# 2_Thermal_stability.net
KiCad netlist of a schematic drawn in Altium Designer
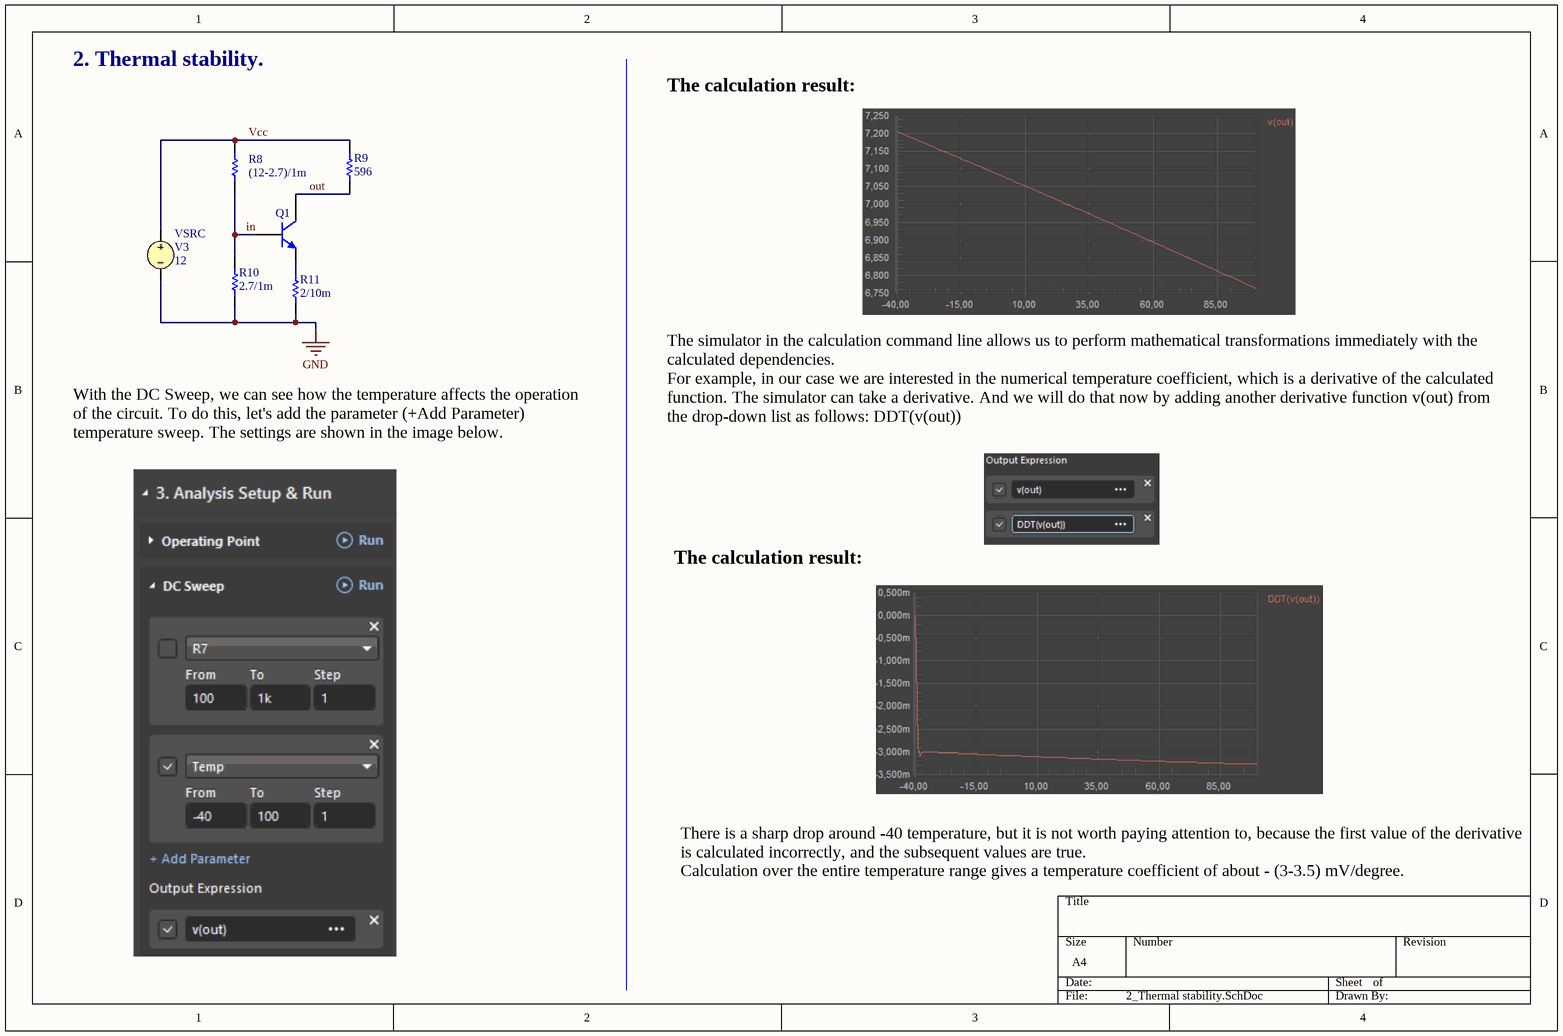
[diagram p0: 2_Thermal stability.SchDoc]

(export (version "E")
  (design (tool "Eeschema 10.0.6"))
  (components
    (comp (ref "Q1")
      (value "Bipolar  NPN 3 Pins  Transistor  Modified Version of the Gummel-Poon Model")
      (libsource (lib "Simulation Generic Components") (part "BJT NPN_MGP"))
    )
    (comp (ref "R8")
      (value "(12-2.7)/1m")
      (description "Resistor")
      (libsource (lib "Simulation Generic Components") (part "Resistor"))
    )
    (comp (ref "R9")
      (value "596")
      (description "Resistor")
      (libsource (lib "Simulation Generic Components") (part "Resistor"))
    )
    (comp (ref "R10")
      (value "2.7/1m")
      (description "Resistor")
      (libsource (lib "Simulation Generic Components") (part "Resistor"))
    )
    (comp (ref "R11")
      (value "2/10m")
      (description "Resistor")
      (libsource (lib "Simulation Generic Components") (part "Resistor"))
    )
    (comp (ref "V3")
      (value "VSRC")
      (description "Voltage Source")
      (fields (field (name "ALTIUM_VALUE") "12") (field (name "PUBLISHER") "Altium Limited"))
      (libsource (lib "Simulation Generic Components") (part "VSRC"))
    )
  )
  (nets
    (net (code "1") (name "/Vcc") (class "Default")
      (node (ref "R8") (pin "2") (pinfunction "2_2") (pintype "passive"))
      (node (ref "R9") (pin "2") (pinfunction "2_2") (pintype "passive"))
      (node (ref "V3") (pin "1") (pinfunction "1_1") (pintype "passive"))
    )
    (net (code "2") (name "/in") (class "Default")
      (node (ref "Q1") (pin "2") (pinfunction "B_2") (pintype "passive"))
      (node (ref "R10") (pin "1") (pinfunction "1_1") (pintype "passive"))
      (node (ref "R8") (pin "1") (pinfunction "1_1") (pintype "passive"))
    )
    (net (code "3") (name "/out") (class "Default")
      (node (ref "Q1") (pin "1") (pinfunction "C_1") (pintype "passive"))
      (node (ref "R9") (pin "1") (pinfunction "1_1") (pintype "passive"))
    )
    (net (code "4") (name "GND") (class "Default")
      (node (ref "R10") (pin "2") (pinfunction "2_2") (pintype "passive"))
      (node (ref "R11") (pin "1") (pinfunction "1_1") (pintype "passive"))
      (node (ref "V3") (pin "2") (pinfunction "2_2") (pintype "passive"))
    )
    (net (code "5") (name "Net-(Q1-E)") (class "Default")
      (node (ref "Q1") (pin "3") (pinfunction "E_3") (pintype "passive"))
      (node (ref "R11") (pin "2") (pinfunction "2_2") (pintype "passive"))
    )
  )
)
